# temt6000-v10.net
KiCad netlist of a schematic drawn in EAGLE
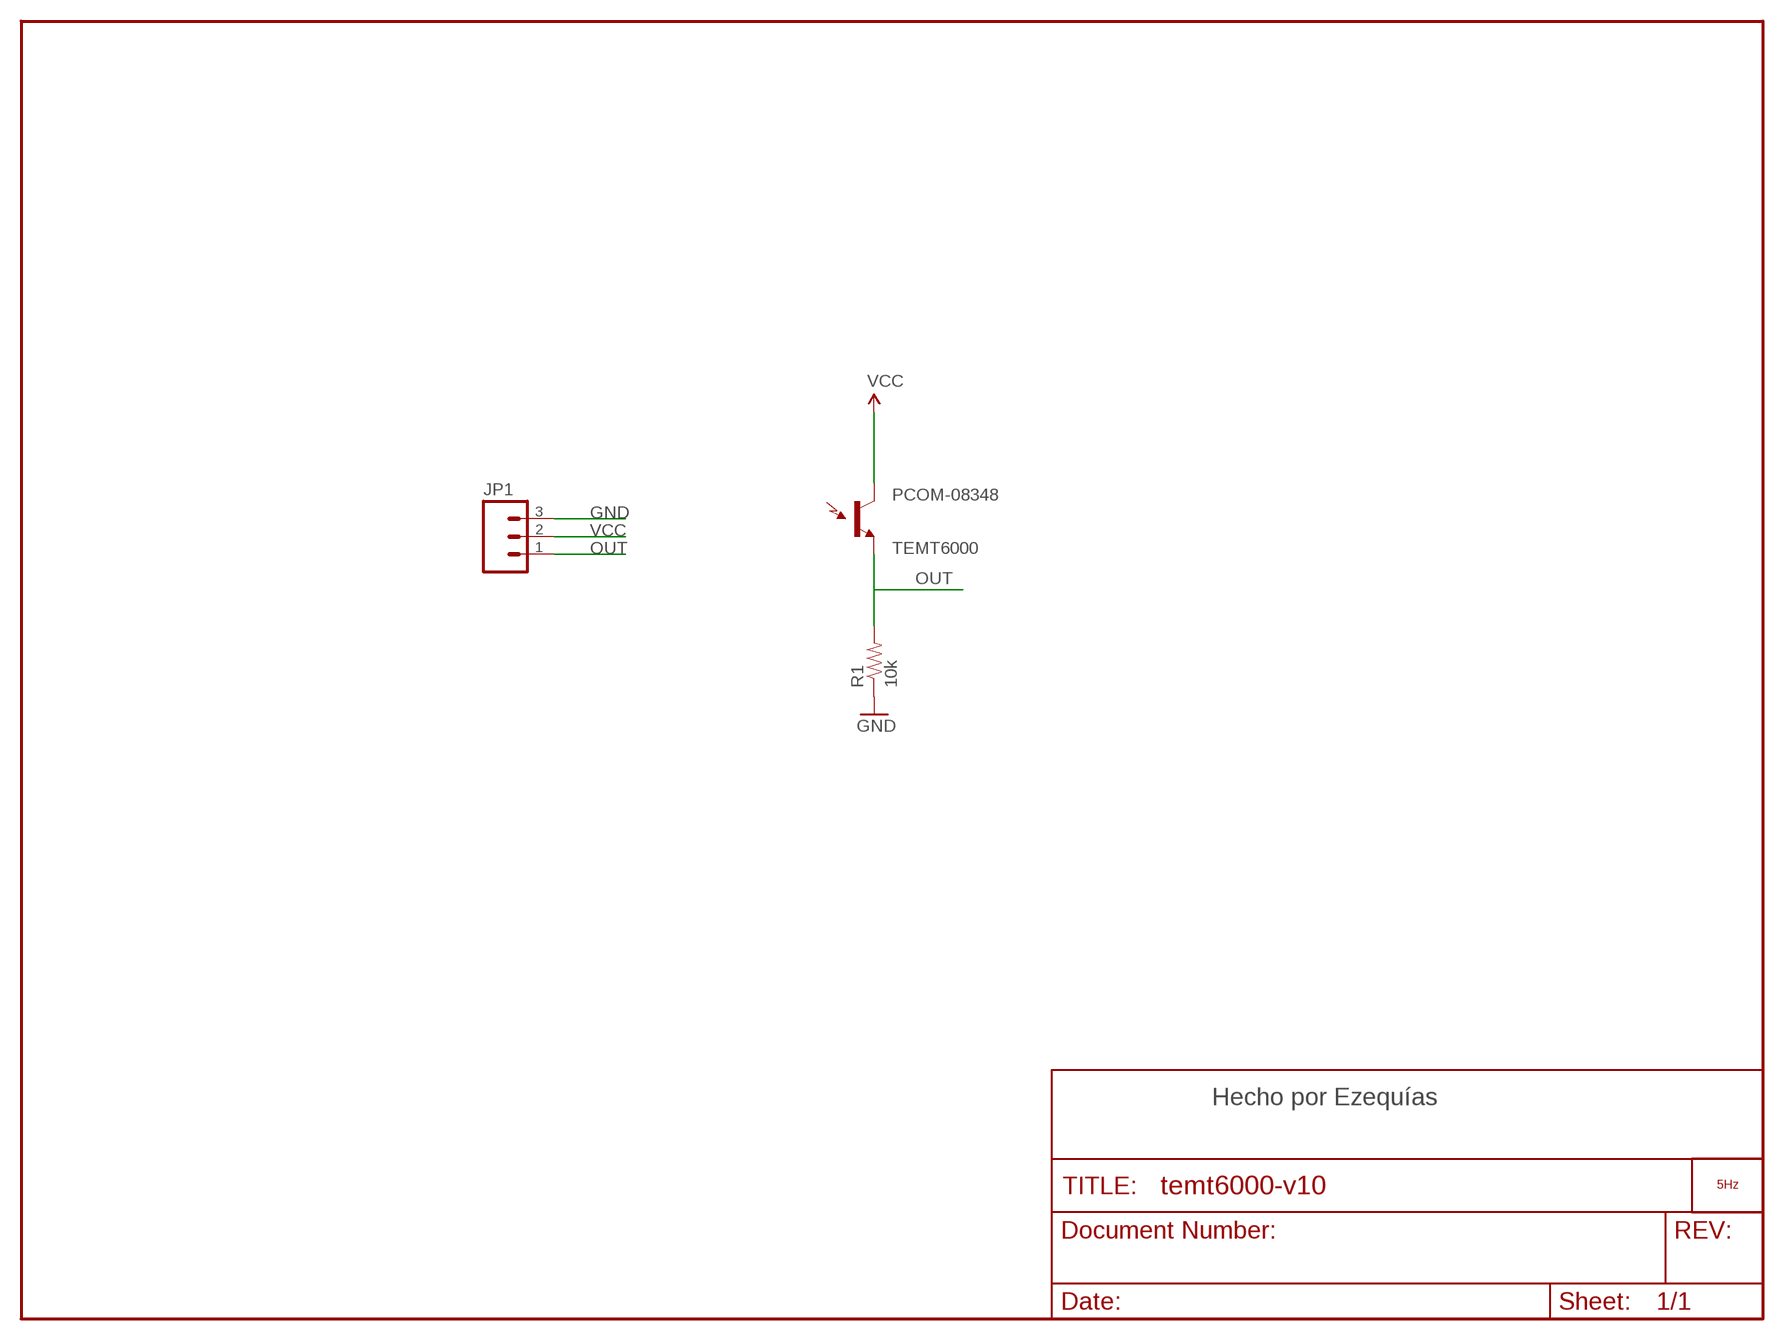
[diagram p0: schematic, sheet 1]

(export (version "E")
  (design (tool "Eeschema 10.0.6"))
  (components
    (comp (ref "JP1")
      (value "M03PTH")
      (footprint "eagle-import:1X03")
      (libsource (lib "eagle-import") (part "M03PTH"))
    )
    (comp (ref "LOGO1")
      (value "LOGO_5HZ_H_5MM")
      (footprint "eagle-import:5HZ_LOGO_H_5MM")
      (libsource (lib "eagle-import") (part "LOGO_5HZ_H_5MM"))
    )
    (comp (ref "PCOM-08348")
      (value "TEMT6000")
      (footprint "eagle-import:TEMT6000-SEN")
      (libsource (lib "eagle-import") (part "TEMT6000"))
    )
    (comp (ref "R1")
      (value "10k")
      (footprint "eagle-import:0603-RES")
      (libsource (lib "eagle-import") (part "RESISTOR0603-RES"))
    )
  )
  (nets
    (net (code "1") (name "/OUT") (class "Default")
      (node (ref "JP1") (pin "1") (pinfunction "1_1") (pintype "passive"))
      (node (ref "PCOM-08348") (pin "EMITTER") (pinfunction "E1_EMITTER") (pintype "passive"))
      (node (ref "R1") (pin "2") (pinfunction "2_2") (pintype "passive"))
    )
    (net (code "2") (name "GND") (class "Default")
      (node (ref "JP1") (pin "3") (pinfunction "3_3") (pintype "passive"))
      (node (ref "R1") (pin "1") (pinfunction "1_1") (pintype "passive"))
    )
    (net (code "3") (name "VCC") (class "Default")
      (node (ref "JP1") (pin "2") (pinfunction "2_2") (pintype "passive"))
      (node (ref "PCOM-08348") (pin "COLLECTOR") (pinfunction "C1_COLLECTOR") (pintype "passive"))
    )
  )
)
